# attenuator.net
KiCad netlist of a schematic drawn in Altium Designer
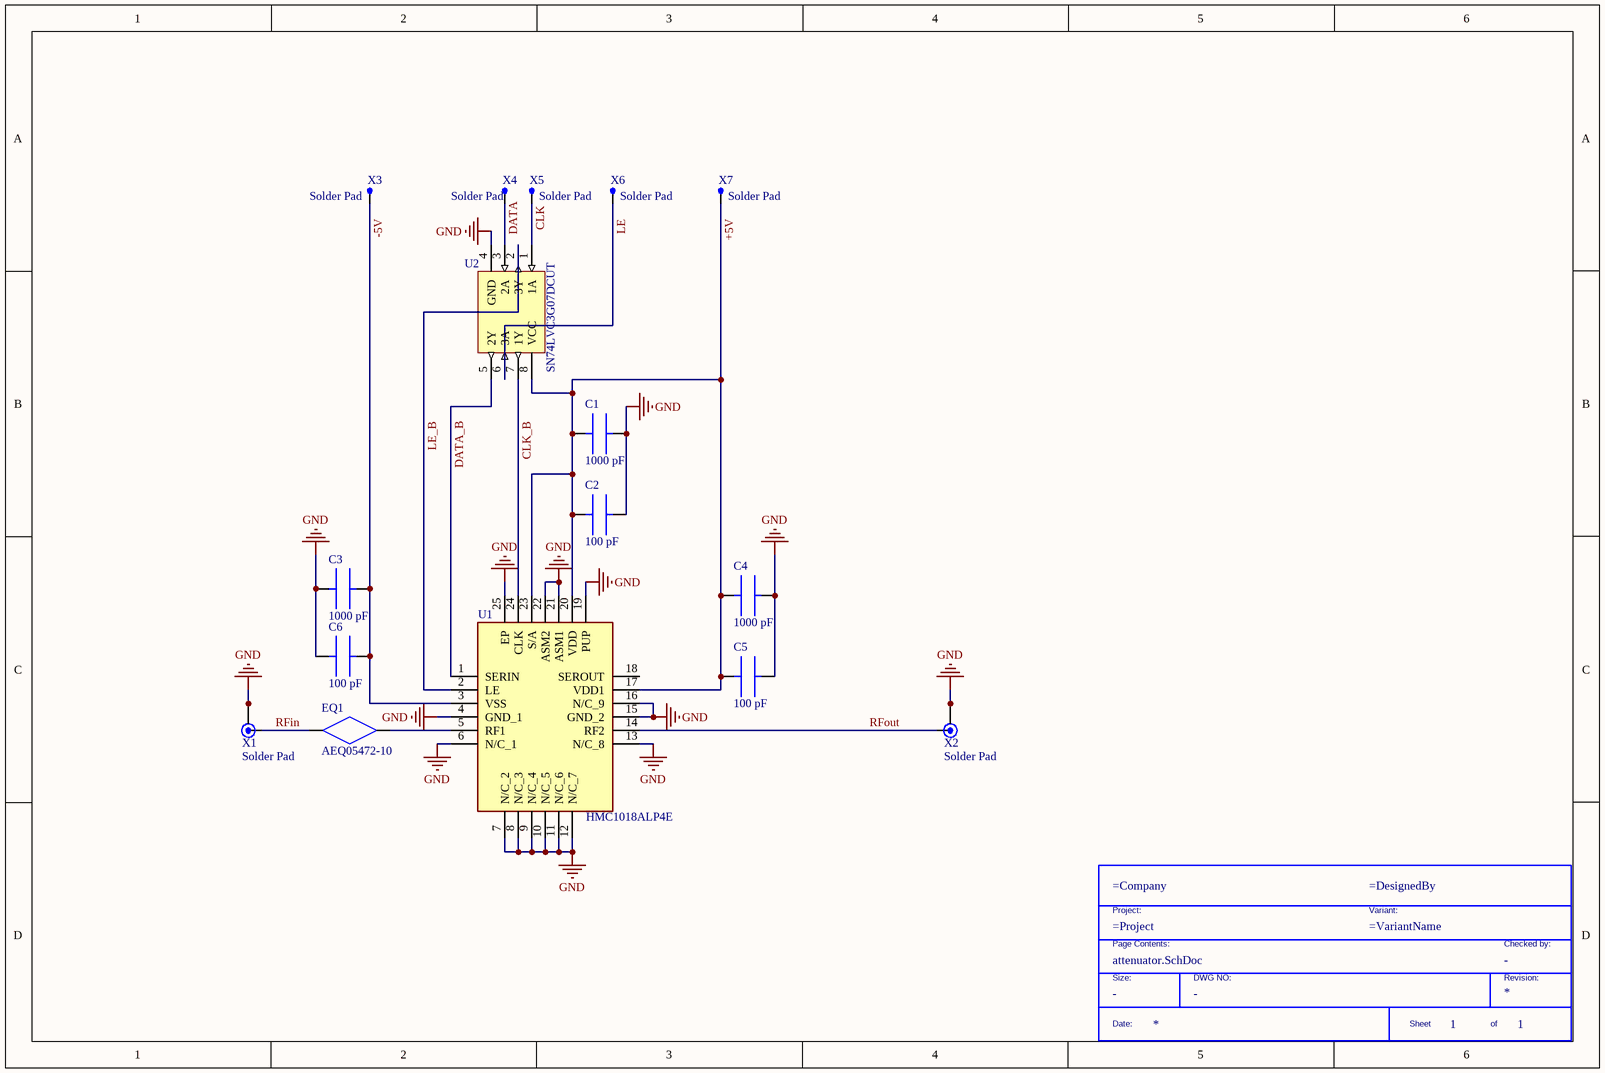
[diagram p0: attenuator.SchDoc]

(export (version "E")
  (design (tool "Eeschema 10.0.6"))
  (components
    (comp (ref "*")
      (value "TitleBlock")
      (description "Standard Title Block")
      (fields (field (name "DWG NO") "-") (field (name "SIZE") "-") (field (name "CHECKED BY") "-"))
      (libsource (lib "amp") (part "TitleBlock"))
    )
    (comp (ref "C1")
      (value "1000 pF")
      (footprint "C1000pF__C100nF")
      (fields
        (field (name "MANUFACTURER") "Murata")
        (field (name "MANUFACTURER PART NUMBER") "GCM1885C1H102FA16D")
      )
      (libsource (lib "attenuator") (part "C1000pF_GCM1885C1H102FA16D"))
    )
    (comp (ref "C2")
      (value "100 pF")
      (footprint "C100pF")
      (description "Multilayer Ceramic Capacitors MLCC - SMD/SMT 100 pF 100 VDC 1% 0402 C0G (NP0)")
      (fields
        (field (name "MANUFACTURER") "Murata")
        (field (name "MANUFACTURER PART NUMBER") "GRM1555C2A101FA01D")
      )
      (libsource (lib "attenuator") (part "C100pF_GRM1555C2A101FA01D"))
    )
    (comp (ref "C3")
      (value "1000 pF")
      (footprint "C1000pF__C100nF")
      (fields
        (field (name "MANUFACTURER") "Murata")
        (field (name "MANUFACTURER PART NUMBER") "GCM1885C1H102FA16D")
      )
      (libsource (lib "attenuator") (part "C1000pF_GCM1885C1H102FA16D"))
    )
    (comp (ref "C4")
      (value "1000 pF")
      (footprint "C1000pF__C100nF")
      (fields
        (field (name "MANUFACTURER") "Murata")
        (field (name "MANUFACTURER PART NUMBER") "GCM1885C1H102FA16D")
      )
      (libsource (lib "attenuator") (part "C1000pF_GCM1885C1H102FA16D"))
    )
    (comp (ref "C5")
      (value "100 pF")
      (footprint "C100pF")
      (description "Multilayer Ceramic Capacitors MLCC - SMD/SMT 100 pF 100 VDC 1% 0402 C0G (NP0)")
      (fields
        (field (name "MANUFACTURER") "Murata")
        (field (name "MANUFACTURER PART NUMBER") "GRM1555C2A101FA01D")
      )
      (libsource (lib "attenuator") (part "C100pF_GRM1555C2A101FA01D"))
    )
    (comp (ref "C6")
      (value "100 pF")
      (footprint "C100pF")
      (description "Multilayer Ceramic Capacitors MLCC - SMD/SMT 100 pF 100 VDC 1% 0402 C0G (NP0)")
      (fields
        (field (name "MANUFACTURER") "Murata")
        (field (name "MANUFACTURER PART NUMBER") "GRM1555C2A101FA01D")
      )
      (libsource (lib "attenuator") (part "C100pF_GRM1555C2A101FA01D"))
    )
    (comp (ref "EQ1")
      (value "AEQ05472-10")
      (footprint "EQ_AEQ05472")
      (description "Rf Filter Gain Equalizer 2SMD")
      (fields (field (name "MANUFACTURER") "Knowles Dielectric Labs"))
      (libsource (lib "amp") (part "EQ_AEQ05472-10"))
    )
    (comp (ref "U1")
      (value "HMC1018ALP4E")
      (footprint "Att_HMC101018ALPE")
      (description "Attenuators Attenuators")
      (fields (field (name "MOUSER PART NUMBER") "584-HMC1018ALP4E"))
      (libsource (lib "attenuator") (part "Att_HMC1018ALP4E"))
    )
    (comp (ref "U2")
      (value "SN74LVC3G07DCUT")
      (footprint "Buf_SN74LVC3G07DCUT")
      (description "Buffer, LVC/LCX/Z Series, 3-Func, 1-Input, CMOS, PDSO8")
      (fields (field (name "MANUFACTURER") "Texas Instruments"))
      (libsource (lib "attenuator") (part "Buf_SN74LVC3G07DCUT"))
    )
    (comp (ref "X1")
      (value "Solder Pad")
      (footprint "CPW Edge Connector")
      (description "Solder pad for RF Coplanar Waveguide Rogers 4350B Thickness 0.020\" Copper 1oz")
      (libsource (lib "amp") (part "RF  CPW Solder Pad"))
    )
    (comp (ref "X2")
      (value "Solder Pad")
      (footprint "CPW Edge Connector")
      (description "Solder pad for RF Coplanar Waveguide Rogers 4350B Thickness 0.020\" Copper 1oz")
      (libsource (lib "amp") (part "RF  CPW Solder Pad"))
    )
    (comp (ref "X3")
      (value "Solder Pad")
      (footprint "Solder Pad")
      (description "Pad to solder wires to")
      (libsource (lib "attenuator") (part "Solder Pad"))
    )
    (comp (ref "X4")
      (value "Solder Pad")
      (footprint "Solder Pad")
      (description "Pad to solder wires to")
      (libsource (lib "attenuator") (part "Solder Pad"))
    )
    (comp (ref "X5")
      (value "Solder Pad")
      (footprint "Solder Pad")
      (description "Pad to solder wires to")
      (libsource (lib "attenuator") (part "Solder Pad"))
    )
    (comp (ref "X6")
      (value "Solder Pad")
      (footprint "Solder Pad")
      (description "Pad to solder wires to")
      (libsource (lib "attenuator") (part "Solder Pad"))
    )
    (comp (ref "X7")
      (value "Solder Pad")
      (footprint "Solder Pad")
      (description "Pad to solder wires to")
      (libsource (lib "amp") (part "Solder Pad"))
    )
  )
  (nets
    (net (code "1") (name "/+5V") (class "Default")
      (node (ref "C1") (pin "1") (pinfunction "1_1") (pintype "passive"))
      (node (ref "C2") (pin "1") (pinfunction "1_1") (pintype "passive"))
      (node (ref "C4") (pin "1") (pinfunction "1_1") (pintype "passive"))
      (node (ref "C5") (pin "1") (pinfunction "1_1") (pintype "passive"))
      (node (ref "U1") (pin "17") (pinfunction "VDD1_17") (pintype "passive"))
      (node (ref "U1") (pin "20") (pinfunction "VDD_20") (pintype "passive"))
      (node (ref "U1") (pin "23") (pinfunction "S/A_23") (pintype "passive"))
      (node (ref "U2") (pin "8") (pinfunction "VCC_8") (pintype "passive"))
      (node (ref "X7") (pin "1") (pinfunction "1_1") (pintype "passive"))
    )
    (net (code "2") (name "/-5V") (class "Default")
      (node (ref "C3") (pin "2") (pinfunction "2_2") (pintype "passive"))
      (node (ref "C6") (pin "2") (pinfunction "2_2") (pintype "passive"))
      (node (ref "U1") (pin "3") (pinfunction "VSS_3") (pintype "passive"))
      (node (ref "X3") (pin "1") (pinfunction "1_1") (pintype "passive"))
    )
    (net (code "3") (name "/CLK") (class "Default")
      (node (ref "U2") (pin "1") (pinfunction "1A_1") (pintype "input"))
      (node (ref "X5") (pin "1") (pinfunction "1_1") (pintype "passive"))
    )
    (net (code "4") (name "/CLK_B") (class "Default")
      (node (ref "U1") (pin "24") (pinfunction "CLK_24") (pintype "passive"))
      (node (ref "U2") (pin "7") (pinfunction "1Y_7") (pintype "output"))
    )
    (net (code "5") (name "/DATA") (class "Default")
      (node (ref "U2") (pin "3") (pinfunction "2A_3") (pintype "input"))
      (node (ref "X4") (pin "1") (pinfunction "1_1") (pintype "passive"))
    )
    (net (code "6") (name "/DATA_B") (class "Default")
      (node (ref "U1") (pin "1") (pinfunction "SERIN_1") (pintype "passive"))
      (node (ref "U2") (pin "5") (pinfunction "2Y_5") (pintype "output"))
    )
    (net (code "7") (name "/LE") (class "Default")
      (node (ref "U2") (pin "6") (pinfunction "3A_6") (pintype "input"))
      (node (ref "X6") (pin "1") (pinfunction "1_1") (pintype "passive"))
    )
    (net (code "8") (name "/LE_B") (class "Default")
      (node (ref "U1") (pin "2") (pinfunction "LE_2") (pintype "passive"))
      (node (ref "U2") (pin "2") (pinfunction "3Y_2") (pintype "output"))
    )
    (net (code "9") (name "/RFin") (class "Default")
      (node (ref "EQ1") (pin "1") (pinfunction "1_1") (pintype "passive"))
      (node (ref "X1") (pin "1") (pinfunction "1_1") (pintype "passive"))
    )
    (net (code "10") (name "/RFout") (class "Default")
      (node (ref "U1") (pin "14") (pinfunction "RF2_14") (pintype "passive"))
      (node (ref "X2") (pin "1") (pinfunction "1_1") (pintype "passive"))
    )
    (net (code "11") (name "GND") (class "Default")
      (node (ref "C1") (pin "2") (pinfunction "2_2") (pintype "passive"))
      (node (ref "C2") (pin "2") (pinfunction "2_2") (pintype "passive"))
      (node (ref "C3") (pin "1") (pinfunction "1_1") (pintype "passive"))
      (node (ref "C4") (pin "2") (pinfunction "2_2") (pintype "passive"))
      (node (ref "C5") (pin "2") (pinfunction "2_2") (pintype "passive"))
      (node (ref "C6") (pin "1") (pinfunction "1_1") (pintype "passive"))
      (node (ref "U1") (pin "10") (pinfunction "N/C_5_10") (pintype "passive"))
      (node (ref "U1") (pin "11") (pinfunction "N/C_6_11") (pintype "passive"))
      (node (ref "U1") (pin "12") (pinfunction "N/C_7_12") (pintype "passive"))
      (node (ref "U1") (pin "13") (pinfunction "N/C_8_13") (pintype "passive"))
      (node (ref "U1") (pin "15") (pinfunction "GND_2_15") (pintype "passive"))
      (node (ref "U1") (pin "16") (pinfunction "N/C_9_16") (pintype "passive"))
      (node (ref "U1") (pin "19") (pinfunction "PUP_19") (pintype "passive"))
      (node (ref "U1") (pin "21") (pinfunction "ASM1_21") (pintype "passive"))
      (node (ref "U1") (pin "22") (pinfunction "ASM2_22") (pintype "passive"))
      (node (ref "U1") (pin "25") (pinfunction "EP_25") (pintype "passive"))
      (node (ref "U1") (pin "4") (pinfunction "GND_1_4") (pintype "passive"))
      (node (ref "U1") (pin "6") (pinfunction "N/C_1_6") (pintype "passive"))
      (node (ref "U1") (pin "7") (pinfunction "N/C_2_7") (pintype "passive"))
      (node (ref "U1") (pin "8") (pinfunction "N/C_3_8") (pintype "passive"))
      (node (ref "U1") (pin "9") (pinfunction "N/C_4_9") (pintype "passive"))
      (node (ref "U2") (pin "4") (pinfunction "GND_4") (pintype "passive"))
      (node (ref "X1") (pin "2") (pinfunction "2_2") (pintype "passive"))
      (node (ref "X1") (pin "3") (pinfunction "3_3") (pintype "passive"))
      (node (ref "X2") (pin "2") (pinfunction "2_2") (pintype "passive"))
      (node (ref "X2") (pin "3") (pinfunction "3_3") (pintype "passive"))
    )
    (net (code "12") (name "Net-(U1-RF1)") (class "Default")
      (node (ref "EQ1") (pin "2") (pinfunction "2_2") (pintype "passive"))
      (node (ref "U1") (pin "5") (pinfunction "RF1_5") (pintype "passive"))
    )
    (net (code "13") (name "unconnected-(U1-SEROUT-Pad18)") (class "Default")
      (node (ref "U1") (pin "18") (pinfunction "SEROUT_18") (pintype "passive"))
    )
  )
)
